# VoltageMeasurement.net
KiCad netlist of a schematic drawn in Altium Designer
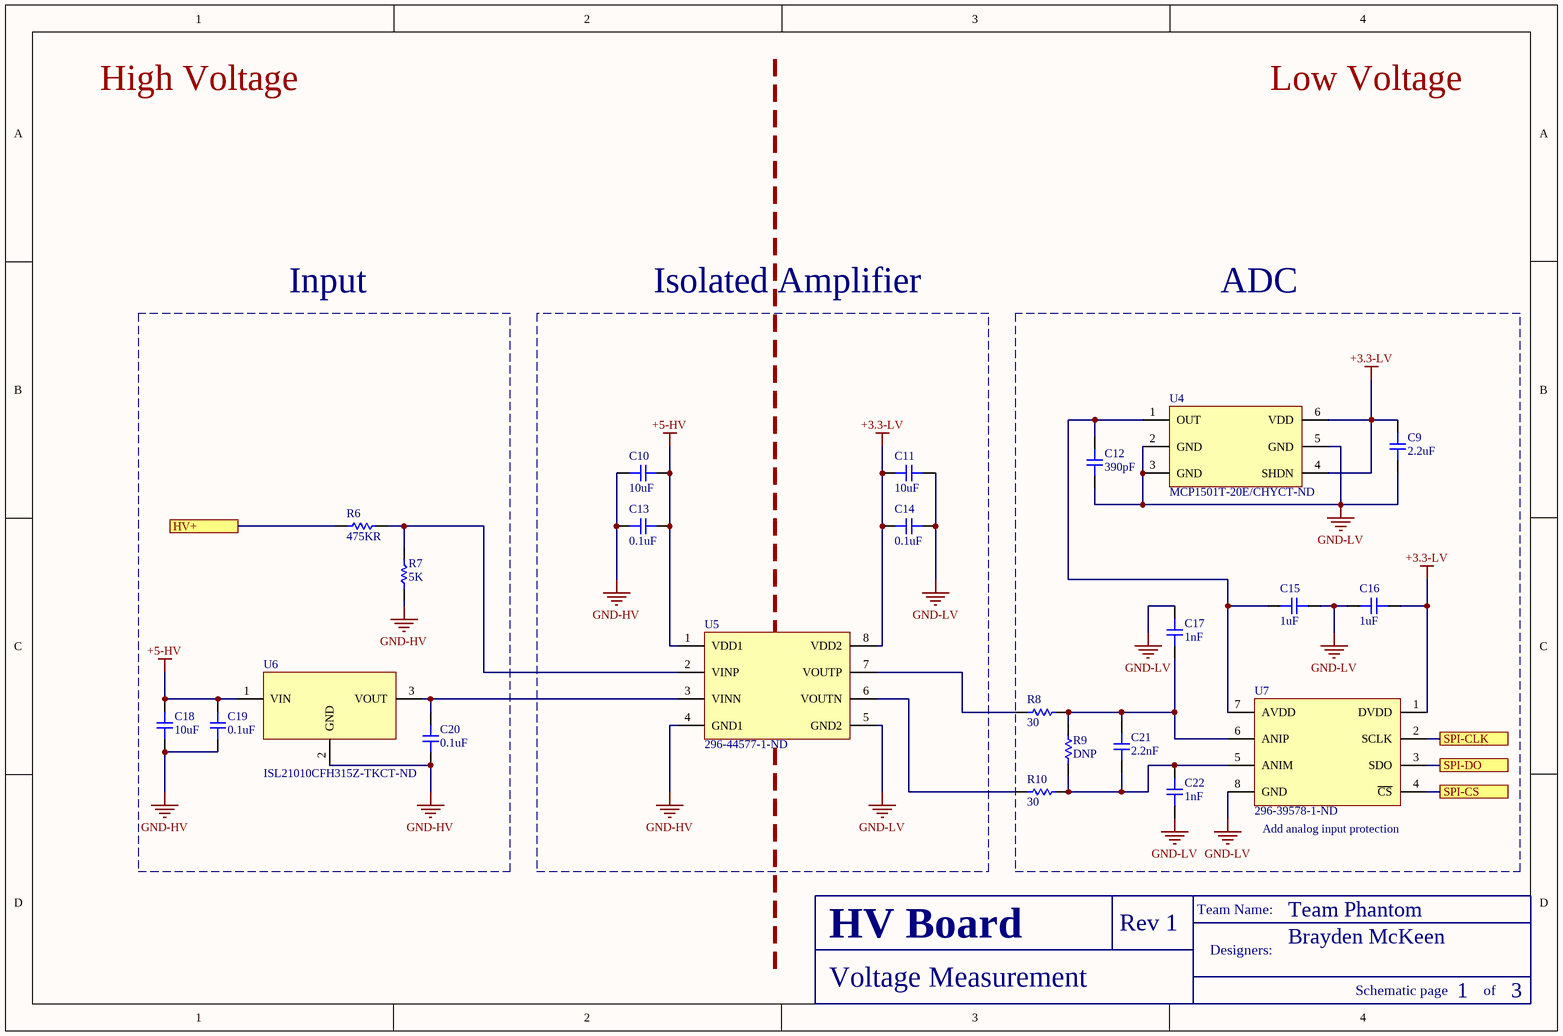
[diagram p0: VoltageMeasurement.SchDoc]

(export (version "E")
  (design (tool "Eeschema 10.0.6"))
  (components
    (comp (ref "C9")
      (value "2.2uF")
      (footprint "CAP-0603")
      (description "CAP CER 2.2UF 25V X5R 0603")
      (fields
        (field (name "MANUFACTURER") "Murata")
        (field (name "MANUFACTURER PART NUMBER") "GRM188R61E225MA12D")
      )
      (libsource (lib "Capacitors") (part "0603-2.2uF-25V"))
    )
    (comp (ref "C10")
      (value "10uF")
      (footprint "CAP-1206")
      (description "CAP CER 10UF 50V X5R 1206")
      (fields
        (field (name "MANUFACTURER") "Murata")
        (field (name "MANUFACTURER PART NUMBER") "GRT31CR61H106ME01L")
      )
      (libsource (lib "Capacitors") (part "1206-10uF-50V"))
    )
    (comp (ref "C11")
      (value "10uF")
      (footprint "CAP-1206")
      (description "CAP CER 10UF 50V X5R 1206")
      (fields
        (field (name "MANUFACTURER") "Murata")
        (field (name "MANUFACTURER PART NUMBER") "GRT31CR61H106ME01L")
      )
      (libsource (lib "Capacitors") (part "1206-10uF-50V"))
    )
    (comp (ref "C12")
      (value "390pF")
      (footprint "CAP-0805")
      (description "CAP CER 390PF 50V C0G/NP0 0805")
      (fields
        (field (name "MANUFACTURER") "KEMET")
        (field (name "MANUFACTURER PART NUMBER") "C0805C391J5GACTU")
      )
      (libsource (lib "Capacitors") (part "0805-390pF-50V"))
    )
    (comp (ref "C13")
      (value "0.1uF")
      (footprint "CAP-0805")
      (description "CAP CER 0.1UF 16V Y5V 0805")
      (fields
        (field (name "MANUFACTURER") "KEMET")
        (field (name "MANUFACTURER PART NUMBER") "C0805C104Z4VACTU")
      )
      (libsource (lib "Capacitors") (part "0805-0.1uF-16V"))
    )
    (comp (ref "C14")
      (value "0.1uF")
      (footprint "CAP-0805")
      (description "CAP CER 0.1UF 16V Y5V 0805")
      (fields
        (field (name "MANUFACTURER") "KEMET")
        (field (name "MANUFACTURER PART NUMBER") "C0805C104Z4VACTU")
      )
      (libsource (lib "Capacitors") (part "0805-0.1uF-16V"))
    )
    (comp (ref "C15")
      (value "1uF")
      (footprint "CAP-0805")
      (description "CAP CER 1UF 16V Y5V 0805")
      (fields
        (field (name "MANUFACTURER") "KEMET")
        (field (name "MANUFACTURER PART NUMBER") "C0805C105Z4VACTU")
      )
      (libsource (lib "") (part "0805-1uF-16V_1"))
    )
    (comp (ref "C16")
      (value "1uF")
      (footprint "CAP-0805")
      (description "CAP CER 1UF 16V Y5V 0805")
      (fields
        (field (name "MANUFACTURER") "KEMET")
        (field (name "MANUFACTURER PART NUMBER") "C0805C105Z4VACTU")
      )
      (libsource (lib "Capacitors") (part "0805-1uF-16V"))
    )
    (comp (ref "C17")
      (value "1nF")
      (footprint "CAP-0603")
      (description "CAP CER 1000PF 50V X7R 0603")
      (fields
        (field (name "MANUFACTURER") "KEMET")
        (field (name "MANUFACTURER PART NUMBER") "C0603C102J5RACTU")
      )
      (libsource (lib "Capacitors") (part "0603-1nF-50V"))
    )
    (comp (ref "C18")
      (value "10uF")
      (footprint "CAP-1206")
      (description "CAP CER 10UF 50V X5R 1206")
      (fields
        (field (name "MANUFACTURER") "Murata")
        (field (name "MANUFACTURER PART NUMBER") "GRT31CR61H106ME01L")
      )
      (libsource (lib "Capacitors") (part "1206-10uF-50V"))
    )
    (comp (ref "C19")
      (value "0.1uF")
      (footprint "CAP-0805")
      (description "CAP CER 0.1UF 16V Y5V 0805")
      (fields
        (field (name "MANUFACTURER") "KEMET")
        (field (name "MANUFACTURER PART NUMBER") "C0805C104Z4VACTU")
      )
      (libsource (lib "Capacitors") (part "0805-0.1uF-16V"))
    )
    (comp (ref "C20")
      (value "0.1uF")
      (footprint "CAP-0805")
      (description "CAP CER 0.1UF 16V Y5V 0805")
      (fields
        (field (name "MANUFACTURER") "KEMET")
        (field (name "MANUFACTURER PART NUMBER") "C0805C104Z4VACTU")
      )
      (libsource (lib "Capacitors") (part "0805-0.1uF-16V"))
    )
    (comp (ref "C21")
      (value "2.2nF")
      (footprint "CAP-0603")
      (description "CAP CER SMD 0603 2200PF 10% X7R")
      (fields
        (field (name "MANUFACTURER") "KEMET")
        (field (name "MANUFACTURER PART NUMBER") "C0603C222K5RAC7411")
      )
      (libsource (lib "Capacitors") (part "0603-2.2nF-50V"))
    )
    (comp (ref "C22")
      (value "1nF")
      (footprint "CAP-0603")
      (description "CAP CER 1000PF 50V X7R 0603")
      (fields
        (field (name "MANUFACTURER") "KEMET")
        (field (name "MANUFACTURER PART NUMBER") "C0603C102J5RACTU")
      )
      (libsource (lib "Capacitors") (part "0603-1nF-50V"))
    )
    (comp (ref "R6")
      (value "475KR")
      (footprint "RES-0805")
      (description "RES 475K OHM 0.1% 1/8W 0805")
      (libsource (lib "Resistors") (part "0805-475KR"))
    )
    (comp (ref "R7")
      (value "5K")
      (footprint "RES-0603")
      (description "RES SMD 4.99K OHM 1% 1/10W 0603")
      (fields
        (field (name "MANUFACTURER") "Bourns")
        (field (name "MANUFACTURER PART NUMBER") "CR0603-FX-4991ELF")
      )
      (libsource (lib "Resistors") (part "0603-5KR"))
    )
    (comp (ref "R8")
      (value "30")
      (footprint "RES-0805")
      (description "RES SMD 30 OHM 1% 1/8W 0805")
      (libsource (lib "Resistors") (part "0805-30R"))
    )
    (comp (ref "R9") (value "DNP") (footprint "RES-0805") (libsource (lib "Resistors") (part "DNP")))
    (comp (ref "R10")
      (value "30")
      (footprint "RES-0805")
      (description "RES SMD 30 OHM 1% 1/8W 0805")
      (libsource (lib "Resistors") (part "0805-30R"))
    )
    (comp (ref "U4")
      (value "MCP1501T-20E/CHYCT-ND")
      (footprint "SOT-23-6")
      (description "IC VREF SERIES 0.1% SOT23-6")
      (libsource (lib "ICs") (part "VREF 2.048V 0.1%"))
    )
    (comp (ref "U5")
      (value "296-44577-1-ND")
      (footprint "8-SOICW")
      (description "IC OPAMP ISOLATION 1 CIRC 8SOIC")
      (fields
        (field (name "MANUFACTURER") "Texas Instruments")
        (field (name "MANUFACTURER PART NUMBER") "AMC1301DWVR")
      )
      (libsource (lib "ICs") (part "OPAMP-ISO-AMC1301DWVR"))
    )
    (comp (ref "U6")
      (value "ISL21010CFH315Z-TKCT-ND")
      (footprint "SOT-23-3")
      (description "IC VREF SERIES 0.2% SOT23-3")
      (libsource (lib "ICs") (part "VREF 1.5V 0.2%"))
    )
    (comp (ref "U7")
      (value "296-39578-1-ND")
      (footprint "8VSSOP")
      (description "IC ADC 12BIT SAR 8VSSOP")
      (fields
        (field (name "MANUFACTURER") "Texas Instruments")
        (field (name "MANUFACTURER PART NUMBER") "ADS7044IDCUT")
      )
      (libsource (lib "ICs") (part "ADC-ADS7044IDCUR"))
    )
  )
  (nets
    (net (code "1") (name "+3.3-LV") (class "Default")
      (node (ref "C11") (pin "1") (pinfunction "1_1") (pintype "passive"))
      (node (ref "C14") (pin "1") (pinfunction "1_1") (pintype "passive"))
      (node (ref "C16") (pin "2") (pinfunction "2_2") (pintype "passive"))
      (node (ref "C9") (pin "2") (pinfunction "2_2") (pintype "passive"))
      (node (ref "U4") (pin "4") (pinfunction "SHDN_4") (pintype "passive"))
      (node (ref "U4") (pin "6") (pinfunction "VDD_6") (pintype "passive"))
      (node (ref "U5") (pin "8") (pinfunction "VDD2_8") (pintype "passive"))
      (node (ref "U7") (pin "1") (pinfunction "DVDD_1") (pintype "passive"))
    )
    (net (code "2") (name "+5-HV") (class "Default")
      (node (ref "C10") (pin "2") (pinfunction "2_2") (pintype "passive"))
      (node (ref "C13") (pin "2") (pinfunction "2_2") (pintype "passive"))
      (node (ref "C18") (pin "2") (pinfunction "2_2") (pintype "passive"))
      (node (ref "C19") (pin "2") (pinfunction "2_2") (pintype "passive"))
      (node (ref "U5") (pin "1") (pinfunction "VDD1_1") (pintype "passive"))
      (node (ref "U6") (pin "1") (pinfunction "VIN_1") (pintype "passive"))
    )
    (net (code "3") (name "/HV+") (class "Default")
      (node (ref "R6") (pin "1") (pinfunction "1_1") (pintype "passive"))
    )
    (net (code "4") (name "/SPI-CLK") (class "Default")
      (node (ref "U7") (pin "2") (pinfunction "SCLK_2") (pintype "passive"))
    )
    (net (code "5") (name "/SPI-CS") (class "Default")
      (node (ref "U7") (pin "4") (pinfunction "~{CS}_4") (pintype "passive"))
    )
    (net (code "6") (name "/SPI-DO") (class "Default")
      (node (ref "U7") (pin "3") (pinfunction "SDO_3") (pintype "passive"))
    )
    (net (code "7") (name "GND-HV") (class "Default")
      (node (ref "C10") (pin "1") (pinfunction "1_1") (pintype "passive"))
      (node (ref "C13") (pin "1") (pinfunction "1_1") (pintype "passive"))
      (node (ref "C18") (pin "1") (pinfunction "1_1") (pintype "passive"))
      (node (ref "C19") (pin "1") (pinfunction "1_1") (pintype "passive"))
      (node (ref "C20") (pin "1") (pinfunction "1_1") (pintype "passive"))
      (node (ref "R7") (pin "1") (pinfunction "1_1") (pintype "passive"))
      (node (ref "U5") (pin "4") (pinfunction "GND1_4") (pintype "passive"))
      (node (ref "U6") (pin "2") (pinfunction "GND_2") (pintype "passive"))
    )
    (net (code "8") (name "GND-LV") (class "Default")
      (node (ref "C11") (pin "2") (pinfunction "2_2") (pintype "passive"))
      (node (ref "C12") (pin "1") (pinfunction "1_1") (pintype "passive"))
      (node (ref "C14") (pin "2") (pinfunction "2_2") (pintype "passive"))
      (node (ref "C15") (pin "2") (pinfunction "2_2") (pintype "passive"))
      (node (ref "C16") (pin "1") (pinfunction "1_1") (pintype "passive"))
      (node (ref "C17") (pin "2") (pinfunction "2_2") (pintype "passive"))
      (node (ref "C22") (pin "1") (pinfunction "1_1") (pintype "passive"))
      (node (ref "C9") (pin "1") (pinfunction "1_1") (pintype "passive"))
      (node (ref "U4") (pin "2") (pinfunction "GND_2") (pintype "passive"))
      (node (ref "U4") (pin "3") (pinfunction "GND_3") (pintype "passive"))
      (node (ref "U4") (pin "5") (pinfunction "GND_5") (pintype "passive"))
      (node (ref "U5") (pin "5") (pinfunction "GND2_5") (pintype "passive"))
      (node (ref "U7") (pin "8") (pinfunction "GND_8") (pintype "passive"))
    )
    (net (code "9") (name "Net-(U4-OUT)") (class "Default")
      (node (ref "C12") (pin "2") (pinfunction "2_2") (pintype "passive"))
      (node (ref "C15") (pin "1") (pinfunction "1_1") (pintype "passive"))
      (node (ref "U4") (pin "1") (pinfunction "OUT_1") (pintype "passive"))
      (node (ref "U7") (pin "7") (pinfunction "AVDD_7") (pintype "passive"))
    )
    (net (code "10") (name "Net-(U5-VINN)") (class "Default")
      (node (ref "C20") (pin "2") (pinfunction "2_2") (pintype "passive"))
      (node (ref "U5") (pin "3") (pinfunction "VINN_3") (pintype "passive"))
      (node (ref "U6") (pin "3") (pinfunction "VOUT_3") (pintype "passive"))
    )
    (net (code "11") (name "Net-(U5-VINP)") (class "Default")
      (node (ref "R6") (pin "2") (pinfunction "2_2") (pintype "passive"))
      (node (ref "R7") (pin "2") (pinfunction "2_2") (pintype "passive"))
      (node (ref "U5") (pin "2") (pinfunction "VINP_2") (pintype "passive"))
    )
    (net (code "12") (name "Net-(U5-VOUTN)") (class "Default")
      (node (ref "R10") (pin "1") (pinfunction "1_1") (pintype "passive"))
      (node (ref "U5") (pin "6") (pinfunction "VOUTN_6") (pintype "passive"))
    )
    (net (code "13") (name "Net-(U5-VOUTP)") (class "Default")
      (node (ref "R8") (pin "1") (pinfunction "1_1") (pintype "passive"))
      (node (ref "U5") (pin "7") (pinfunction "VOUTP_7") (pintype "passive"))
    )
    (net (code "14") (name "Net-(U7-ANIM)") (class "Default")
      (node (ref "C21") (pin "1") (pinfunction "1_1") (pintype "passive"))
      (node (ref "C22") (pin "2") (pinfunction "2_2") (pintype "passive"))
      (node (ref "R10") (pin "2") (pinfunction "2_2") (pintype "passive"))
      (node (ref "R9") (pin "1") (pinfunction "1_1") (pintype "passive"))
      (node (ref "U7") (pin "5") (pinfunction "ANIM_5") (pintype "passive"))
    )
    (net (code "15") (name "Net-(U7-ANIP)") (class "Default")
      (node (ref "C17") (pin "1") (pinfunction "1_1") (pintype "passive"))
      (node (ref "C21") (pin "2") (pinfunction "2_2") (pintype "passive"))
      (node (ref "R8") (pin "2") (pinfunction "2_2") (pintype "passive"))
      (node (ref "R9") (pin "2") (pinfunction "2_2") (pintype "passive"))
      (node (ref "U7") (pin "6") (pinfunction "ANIP_6") (pintype "passive"))
    )
  )
)
